# selfcontained_low_power_node_v1.net
KiCad netlist of a schematic drawn in EAGLE
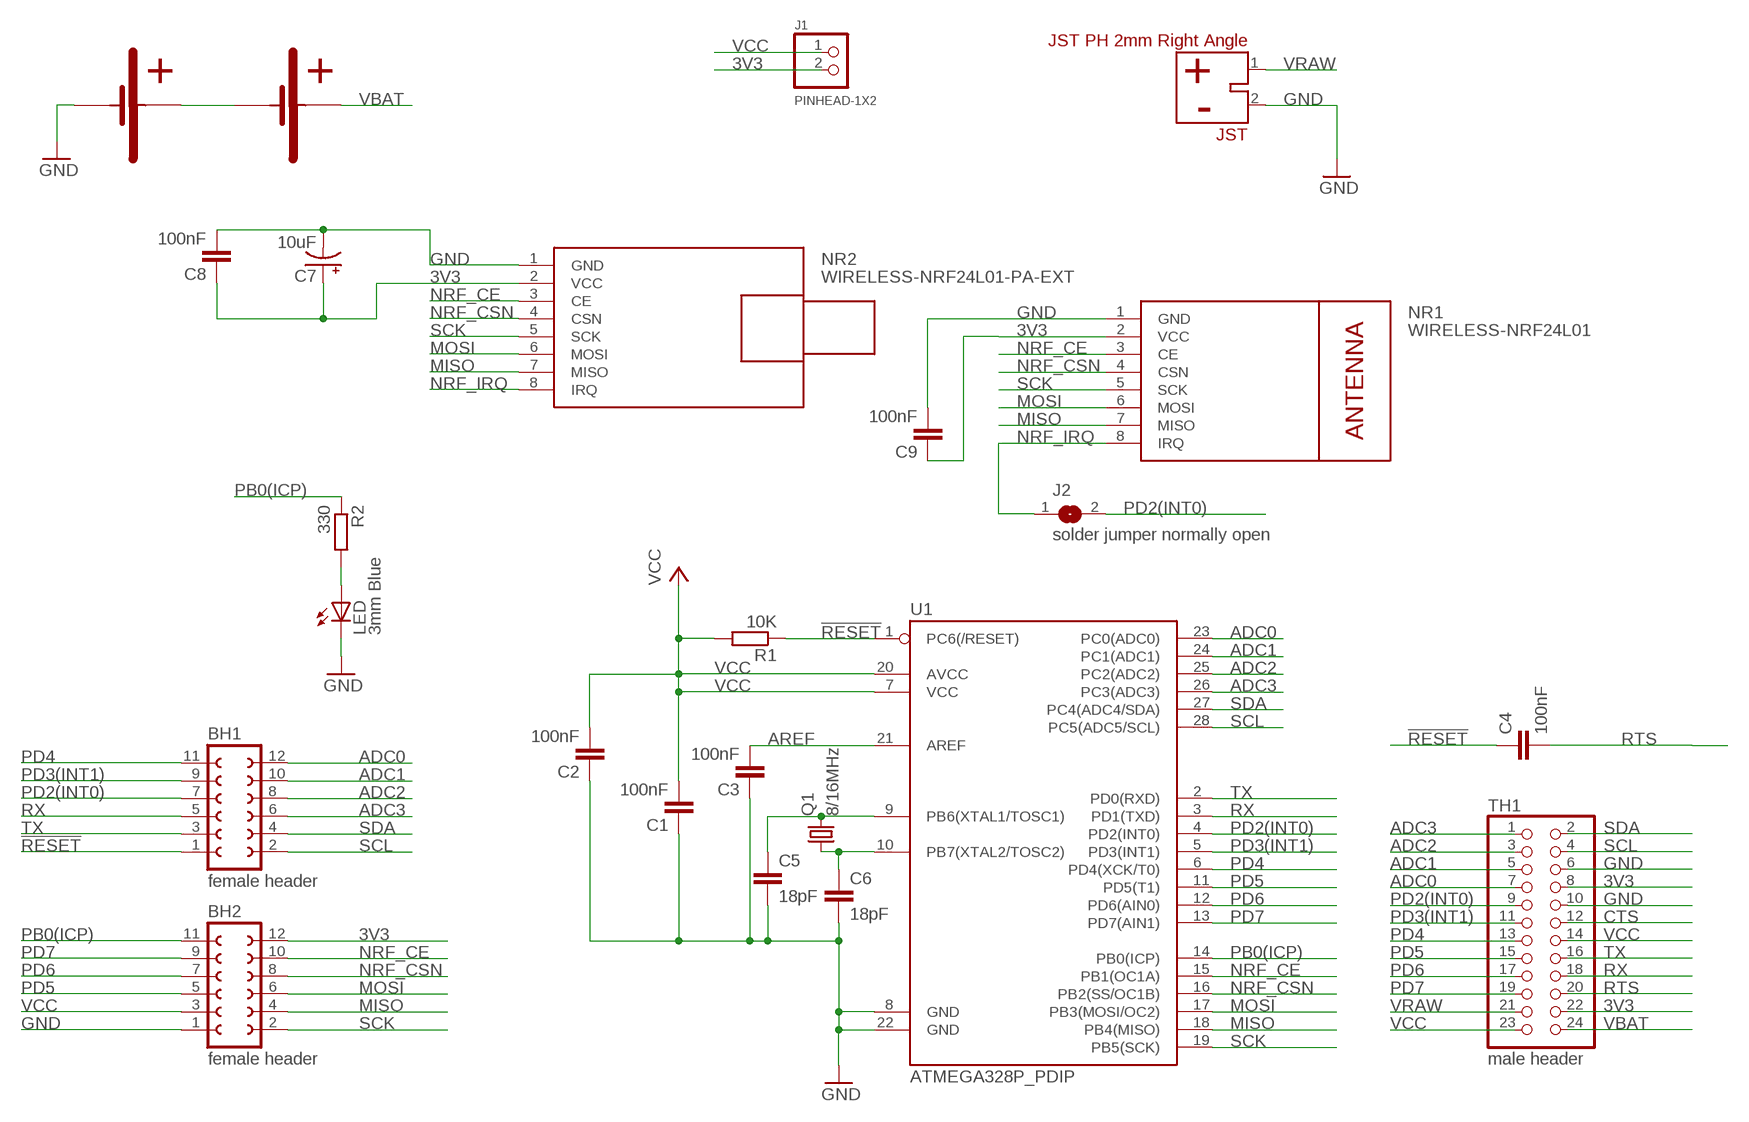
[diagram p0: schematic, sheet 1]

(export (version "E")
  (design (tool "Eeschema 10.0.6"))
  (components
    (comp (ref "BAT1")
      (value "AAABATTERY")
      (footprint "eagle-import:AAABATTERYHOLDER")
      (libsource (lib "eagle-import") (part "AAABATTERY"))
    )
    (comp (ref "BAT2")
      (value "AAABATTERY")
      (footprint "eagle-import:AAABATTERYHOLDER")
      (libsource (lib "eagle-import") (part "AAABATTERY"))
    )
    (comp (ref "BH1")
      (value "female header")
      (footprint "eagle-import:FE06-2")
      (libsource (lib "eagle-import") (part "FE06-2"))
    )
    (comp (ref "BH2")
      (value "female header")
      (footprint "eagle-import:FE06-2")
      (libsource (lib "eagle-import") (part "FE06-2"))
    )
    (comp (ref "C1")
      (value "100nF")
      (footprint "eagle-import:C025-025X050")
      (libsource (lib "eagle-import") (part "resistor_C-EU025-025X050"))
    )
    (comp (ref "C2")
      (value "100nF")
      (footprint "eagle-import:C025-025X050")
      (libsource (lib "eagle-import") (part "resistor_C-EU025-025X050"))
    )
    (comp (ref "C3")
      (value "100nF")
      (footprint "eagle-import:C025-025X050")
      (libsource (lib "eagle-import") (part "resistor_C-EU025-025X050"))
    )
    (comp (ref "C4")
      (value "100nF")
      (footprint "eagle-import:C025-025X050")
      (libsource (lib "eagle-import") (part "resistor_C-EU025-025X050"))
    )
    (comp (ref "C5")
      (value "18pF")
      (footprint "eagle-import:C025_050-024X070")
      (libsource (lib "eagle-import") (part "C-EUC025_050-024X070"))
    )
    (comp (ref "C6")
      (value "18pF")
      (footprint "eagle-import:C025_050-024X070")
      (libsource (lib "eagle-import") (part "C-EUC025_050-024X070"))
    )
    (comp (ref "C7")
      (value "10uF")
      (footprint "eagle-import:E2,5-5")
      (libsource (lib "eagle-import") (part "CPOL-USE2.5-5"))
    )
    (comp (ref "C8")
      (value "100nF")
      (footprint "eagle-import:C025-025X050")
      (libsource (lib "eagle-import") (part "resistor_C-EU025-025X050"))
    )
    (comp (ref "C9")
      (value "100nF")
      (footprint "eagle-import:C025-025X050")
      (libsource (lib "eagle-import") (part "resistor_C-EU025-025X050"))
    )
    (comp (ref "J1")
      (value "PINHEAD-1X2")
      (footprint "eagle-import:PIHEAD-1X2")
      (libsource (lib "eagle-import") (part "PINHEAD-1X2"))
    )
    (comp (ref "J2")
      (value "solder jumper normally open")
      (footprint "eagle-import:SJ")
      (libsource (lib "eagle-import") (part "SJ"))
    )
    (comp (ref "JST")
      (value "JST PH 2mm Right Angle")
      (footprint "eagle-import:JST-PH-2-THM-RA")
      (libsource (lib "eagle-import") (part "JST_2PINJST-PH-2-THM-RA"))
    )
    (comp (ref "LED")
      (value "3mm Blue")
      (footprint "eagle-import:LED3MM")
      (libsource (lib "eagle-import") (part "LED3MM"))
    )
    (comp (ref "NR1")
      (value "WIRELESS-NRF24L01")
      (footprint "eagle-import:WIRELESS-NRF24L01")
      (libsource (lib "eagle-import") (part "WIRELESS-NRF24L01"))
    )
    (comp (ref "NR2")
      (value "WIRELESS-NRF24L01-PA-EXT")
      (footprint "eagle-import:WIRELESS-NRD24L01-PA-EXT")
      (libsource (lib "eagle-import") (part "WIRELESS-NRF24L01-PA-EXT"))
    )
    (comp (ref "Q1")
      (value "8/16MHz")
      (footprint "eagle-import:HC49_S")
      (libsource (lib "eagle-import") (part "CRYSTALHC49S"))
    )
    (comp (ref "R1")
      (value "10K")
      (footprint "eagle-import:0207_2V")
      (libsource (lib "eagle-import") (part "R-EU_0207/2V"))
    )
    (comp (ref "R2")
      (value "330")
      (footprint "eagle-import:0207_2V")
      (libsource (lib "eagle-import") (part "R-EU_0207/2V"))
    )
    (comp (ref "TH1")
      (value "male header")
      (footprint "eagle-import:2X12")
      (libsource (lib "eagle-import") (part "PINHD-2X12"))
    )
    (comp (ref "U1")
      (value "ATMEGA328P_PDIP")
      (footprint "eagle-import:DIL28-3")
      (libsource (lib "eagle-import") (part "ATMEGA328P_PDIP"))
    )
  )
  (nets
    (net (code "1") (name "/3V3") (class "Default")
      (node (ref "BH2") (pin "12") (pinfunction "12_12") (pintype "passive"))
      (node (ref "C7") (pin "+") (pinfunction "+_+") (pintype "passive"))
      (node (ref "C8") (pin "1") (pinfunction "1_1") (pintype "passive"))
      (node (ref "C9") (pin "1") (pinfunction "1_1") (pintype "passive"))
      (node (ref "J1") (pin "2") (pinfunction "2_2") (pintype "passive"))
      (node (ref "NR1") (pin "2") (pinfunction "VCC_2") (pintype "power_in"))
      (node (ref "NR2") (pin "2") (pinfunction "VCC_2") (pintype "power_in"))
      (node (ref "TH1") (pin "22") (pinfunction "22_22") (pintype "passive"))
      (node (ref "TH1") (pin "8") (pinfunction "8_8") (pintype "passive"))
    )
    (net (code "2") (name "/ADC0") (class "Default")
      (node (ref "BH1") (pin "12") (pinfunction "12_12") (pintype "passive"))
      (node (ref "TH1") (pin "7") (pinfunction "7_7") (pintype "passive"))
      (node (ref "U1") (pin "23") (pinfunction "PC0(ADC0)_23") (pintype "bidirectional"))
    )
    (net (code "3") (name "/ADC1") (class "Default")
      (node (ref "BH1") (pin "10") (pinfunction "10_10") (pintype "passive"))
      (node (ref "TH1") (pin "5") (pinfunction "5_5") (pintype "passive"))
      (node (ref "U1") (pin "24") (pinfunction "PC1(ADC1)_24") (pintype "bidirectional"))
    )
    (net (code "4") (name "/ADC2") (class "Default")
      (node (ref "BH1") (pin "8") (pinfunction "8_8") (pintype "passive"))
      (node (ref "TH1") (pin "3") (pinfunction "3_3") (pintype "passive"))
      (node (ref "U1") (pin "25") (pinfunction "PC2(ADC2)_25") (pintype "bidirectional"))
    )
    (net (code "5") (name "/ADC3") (class "Default")
      (node (ref "BH1") (pin "6") (pinfunction "6_6") (pintype "passive"))
      (node (ref "TH1") (pin "1") (pinfunction "1_1") (pintype "passive"))
      (node (ref "U1") (pin "26") (pinfunction "PC3(ADC3)_26") (pintype "bidirectional"))
    )
    (net (code "6") (name "/AREF") (class "Default")
      (node (ref "C3") (pin "2") (pinfunction "2_2") (pintype "passive"))
      (node (ref "U1") (pin "21") (pinfunction "AREF_21") (pintype "bidirectional"))
    )
    (net (code "7") (name "/CTS") (class "Default")
      (node (ref "TH1") (pin "12") (pinfunction "12_12") (pintype "passive"))
    )
    (net (code "8") (name "/MISO") (class "Default")
      (node (ref "BH2") (pin "4") (pinfunction "4_4") (pintype "passive"))
      (node (ref "NR1") (pin "7") (pinfunction "MISO_7") (pintype "bidirectional"))
      (node (ref "NR2") (pin "7") (pinfunction "MISO_7") (pintype "bidirectional"))
      (node (ref "U1") (pin "18") (pinfunction "PB4(MISO)_18") (pintype "bidirectional"))
    )
    (net (code "9") (name "/MOSI") (class "Default")
      (node (ref "BH2") (pin "6") (pinfunction "6_6") (pintype "passive"))
      (node (ref "NR1") (pin "6") (pinfunction "MOSI_6") (pintype "bidirectional"))
      (node (ref "NR2") (pin "6") (pinfunction "MOSI_6") (pintype "bidirectional"))
      (node (ref "U1") (pin "17") (pinfunction "PB3(MOSI/OC2)_17") (pintype "bidirectional"))
    )
    (net (code "10") (name "/NRF_CE") (class "Default")
      (node (ref "BH2") (pin "10") (pinfunction "10_10") (pintype "passive"))
      (node (ref "NR1") (pin "3") (pinfunction "CE_3") (pintype "bidirectional"))
      (node (ref "NR2") (pin "3") (pinfunction "CE_3") (pintype "bidirectional"))
      (node (ref "U1") (pin "15") (pinfunction "PB1(OC1A)_15") (pintype "bidirectional"))
    )
    (net (code "11") (name "/NRF_CSN") (class "Default")
      (node (ref "BH2") (pin "8") (pinfunction "8_8") (pintype "passive"))
      (node (ref "NR1") (pin "4") (pinfunction "CSN_4") (pintype "bidirectional"))
      (node (ref "NR2") (pin "4") (pinfunction "CSN_4") (pintype "bidirectional"))
      (node (ref "U1") (pin "16") (pinfunction "PB2(SS/OC1B)_16") (pintype "bidirectional"))
    )
    (net (code "12") (name "/NRF_IRQ") (class "Default")
      (node (ref "J2") (pin "1") (pinfunction "1_1") (pintype "passive"))
      (node (ref "NR1") (pin "8") (pinfunction "IRQ_8") (pintype "bidirectional"))
      (node (ref "NR2") (pin "8") (pinfunction "IRQ_8") (pintype "bidirectional"))
    )
    (net (code "13") (name "/PB0(ICP)") (class "Default")
      (node (ref "BH2") (pin "11") (pinfunction "11_11") (pintype "passive"))
      (node (ref "R2") (pin "1") (pinfunction "1_1") (pintype "passive"))
      (node (ref "U1") (pin "14") (pinfunction "PB0(ICP)_14") (pintype "bidirectional"))
    )
    (net (code "14") (name "/PD2(INT0)") (class "Default")
      (node (ref "BH1") (pin "7") (pinfunction "7_7") (pintype "passive"))
      (node (ref "J2") (pin "2") (pinfunction "2_2") (pintype "passive"))
      (node (ref "TH1") (pin "9") (pinfunction "9_9") (pintype "passive"))
      (node (ref "U1") (pin "4") (pinfunction "PD2(INT0)_4") (pintype "bidirectional"))
    )
    (net (code "15") (name "/PD3(INT1)") (class "Default")
      (node (ref "BH1") (pin "9") (pinfunction "9_9") (pintype "passive"))
      (node (ref "TH1") (pin "11") (pinfunction "11_11") (pintype "passive"))
      (node (ref "U1") (pin "5") (pinfunction "PD3(INT1)_5") (pintype "bidirectional"))
    )
    (net (code "16") (name "/PD4") (class "Default")
      (node (ref "BH1") (pin "11") (pinfunction "11_11") (pintype "passive"))
      (node (ref "TH1") (pin "13") (pinfunction "13_13") (pintype "passive"))
      (node (ref "U1") (pin "6") (pinfunction "PD4(XCK/T0)_6") (pintype "bidirectional"))
    )
    (net (code "17") (name "/PD5") (class "Default")
      (node (ref "BH2") (pin "5") (pinfunction "5_5") (pintype "passive"))
      (node (ref "TH1") (pin "15") (pinfunction "15_15") (pintype "passive"))
      (node (ref "U1") (pin "11") (pinfunction "PD5(T1)_11") (pintype "bidirectional"))
    )
    (net (code "18") (name "/PD6") (class "Default")
      (node (ref "BH2") (pin "7") (pinfunction "7_7") (pintype "passive"))
      (node (ref "TH1") (pin "17") (pinfunction "17_17") (pintype "passive"))
      (node (ref "U1") (pin "12") (pinfunction "PD6(AIN0)_12") (pintype "bidirectional"))
    )
    (net (code "19") (name "/PD7") (class "Default")
      (node (ref "BH2") (pin "9") (pinfunction "9_9") (pintype "passive"))
      (node (ref "TH1") (pin "19") (pinfunction "19_19") (pintype "passive"))
      (node (ref "U1") (pin "13") (pinfunction "PD7(AIN1)_13") (pintype "bidirectional"))
    )
    (net (code "20") (name "/RTS") (class "Default")
      (node (ref "C4") (pin "2") (pinfunction "2_2") (pintype "passive"))
      (node (ref "TH1") (pin "20") (pinfunction "20_20") (pintype "passive"))
    )
    (net (code "21") (name "/RX") (class "Default")
      (node (ref "BH1") (pin "5") (pinfunction "5_5") (pintype "passive"))
      (node (ref "TH1") (pin "18") (pinfunction "18_18") (pintype "passive"))
      (node (ref "U1") (pin "3") (pinfunction "PD1(TXD)_3") (pintype "bidirectional"))
    )
    (net (code "22") (name "/SCK") (class "Default")
      (node (ref "BH2") (pin "2") (pinfunction "2_2") (pintype "passive"))
      (node (ref "NR1") (pin "5") (pinfunction "SCK_5") (pintype "bidirectional"))
      (node (ref "NR2") (pin "5") (pinfunction "SCK_5") (pintype "bidirectional"))
      (node (ref "U1") (pin "19") (pinfunction "PB5(SCK)_19") (pintype "bidirectional"))
    )
    (net (code "23") (name "/SCL") (class "Default")
      (node (ref "BH1") (pin "2") (pinfunction "2_2") (pintype "passive"))
      (node (ref "TH1") (pin "4") (pinfunction "4_4") (pintype "passive"))
      (node (ref "U1") (pin "28") (pinfunction "PC5(ADC5/SCL)_28") (pintype "bidirectional"))
    )
    (net (code "24") (name "/SDA") (class "Default")
      (node (ref "BH1") (pin "4") (pinfunction "4_4") (pintype "passive"))
      (node (ref "TH1") (pin "2") (pinfunction "2_2") (pintype "passive"))
      (node (ref "U1") (pin "27") (pinfunction "PC4(ADC4/SDA)_27") (pintype "bidirectional"))
    )
    (net (code "25") (name "/TX") (class "Default")
      (node (ref "BH1") (pin "3") (pinfunction "3_3") (pintype "passive"))
      (node (ref "TH1") (pin "16") (pinfunction "16_16") (pintype "passive"))
      (node (ref "U1") (pin "2") (pinfunction "PD0(RXD)_2") (pintype "bidirectional"))
    )
    (net (code "26") (name "/VBAT") (class "Default")
      (node (ref "BAT2") (pin "P$2") (pinfunction "P$2_P$2") (pintype "bidirectional"))
      (node (ref "TH1") (pin "24") (pinfunction "24_24") (pintype "passive"))
    )
    (net (code "27") (name "/VRAW") (class "Default")
      (node (ref "JST") (pin "1") (pinfunction "1_1") (pintype "bidirectional"))
      (node (ref "TH1") (pin "21") (pinfunction "21_21") (pintype "passive"))
    )
    (net (code "28") (name "/~{RESET}") (class "Default")
      (node (ref "BH1") (pin "1") (pinfunction "1_1") (pintype "passive"))
      (node (ref "C4") (pin "1") (pinfunction "1_1") (pintype "passive"))
      (node (ref "R1") (pin "1") (pinfunction "1_1") (pintype "passive"))
      (node (ref "U1") (pin "1") (pinfunction "PC6(/RESET)_1") (pintype "bidirectional"))
    )
    (net (code "29") (name "GND") (class "Default")
      (node (ref "BAT1") (pin "P$1") (pinfunction "P$1_P$1") (pintype "bidirectional"))
      (node (ref "BH2") (pin "1") (pinfunction "1_1") (pintype "passive"))
      (node (ref "C1") (pin "1") (pinfunction "1_1") (pintype "passive"))
      (node (ref "C2") (pin "1") (pinfunction "1_1") (pintype "passive"))
      (node (ref "C3") (pin "1") (pinfunction "1_1") (pintype "passive"))
      (node (ref "C5") (pin "2") (pinfunction "2_2") (pintype "passive"))
      (node (ref "C5") (pin "3") (pinfunction "2_3") (pintype "passive"))
      (node (ref "C6") (pin "2") (pinfunction "2_2") (pintype "passive"))
      (node (ref "C6") (pin "3") (pinfunction "2_3") (pintype "passive"))
      (node (ref "C7") (pin "-") (pinfunction "-_-") (pintype "passive"))
      (node (ref "C8") (pin "2") (pinfunction "2_2") (pintype "passive"))
      (node (ref "C9") (pin "2") (pinfunction "2_2") (pintype "passive"))
      (node (ref "JST") (pin "2") (pinfunction "2_2") (pintype "bidirectional"))
      (node (ref "LED") (pin "K") (pinfunction "C_K") (pintype "passive"))
      (node (ref "NR1") (pin "1") (pinfunction "GND_1") (pintype "power_in"))
      (node (ref "NR2") (pin "1") (pinfunction "GND_1") (pintype "power_in"))
      (node (ref "TH1") (pin "10") (pinfunction "10_10") (pintype "passive"))
      (node (ref "TH1") (pin "6") (pinfunction "6_6") (pintype "passive"))
      (node (ref "U1") (pin "22") (pinfunction "GND_22") (pintype "bidirectional"))
      (node (ref "U1") (pin "8") (pinfunction "GND_8") (pintype "bidirectional"))
    )
    (net (code "30") (name "Net-(BAT1-PadP$2)") (class "Default")
      (node (ref "BAT1") (pin "P$2") (pinfunction "P$2_P$2") (pintype "bidirectional"))
      (node (ref "BAT2") (pin "P$1") (pinfunction "P$1_P$1") (pintype "bidirectional"))
    )
    (net (code "31") (name "Net-(LED-PadA)") (class "Default")
      (node (ref "LED") (pin "A") (pinfunction "A_A") (pintype "passive"))
      (node (ref "R2") (pin "2") (pinfunction "2_2") (pintype "passive"))
    )
    (net (code "32") (name "Net-(U1-PB6(XTAL1{slash}TOSC1))") (class "Default")
      (node (ref "C5") (pin "1") (pinfunction "1_1") (pintype "passive"))
      (node (ref "Q1") (pin "2") (pinfunction "2_2") (pintype "passive"))
      (node (ref "U1") (pin "9") (pinfunction "PB6(XTAL1/TOSC1)_9") (pintype "bidirectional"))
    )
    (net (code "33") (name "Net-(U1-PB7(XTAL2{slash}TOSC2))") (class "Default")
      (node (ref "C6") (pin "1") (pinfunction "1_1") (pintype "passive"))
      (node (ref "Q1") (pin "1") (pinfunction "1_1") (pintype "passive"))
      (node (ref "U1") (pin "10") (pinfunction "PB7(XTAL2/TOSC2)_10") (pintype "bidirectional"))
    )
    (net (code "34") (name "VCC") (class "Default")
      (node (ref "BH2") (pin "3") (pinfunction "3_3") (pintype "passive"))
      (node (ref "C1") (pin "2") (pinfunction "2_2") (pintype "passive"))
      (node (ref "C2") (pin "2") (pinfunction "2_2") (pintype "passive"))
      (node (ref "J1") (pin "1") (pinfunction "1_1") (pintype "passive"))
      (node (ref "R1") (pin "2") (pinfunction "2_2") (pintype "passive"))
      (node (ref "TH1") (pin "14") (pinfunction "14_14") (pintype "passive"))
      (node (ref "TH1") (pin "23") (pinfunction "23_23") (pintype "passive"))
      (node (ref "U1") (pin "20") (pinfunction "AVCC_20") (pintype "bidirectional"))
      (node (ref "U1") (pin "7") (pinfunction "VCC_7") (pintype "bidirectional"))
    )
  )
)
